# m0xpdLooping_ADSR_v2_0.net
KiCad netlist of a schematic drawn in EAGLE
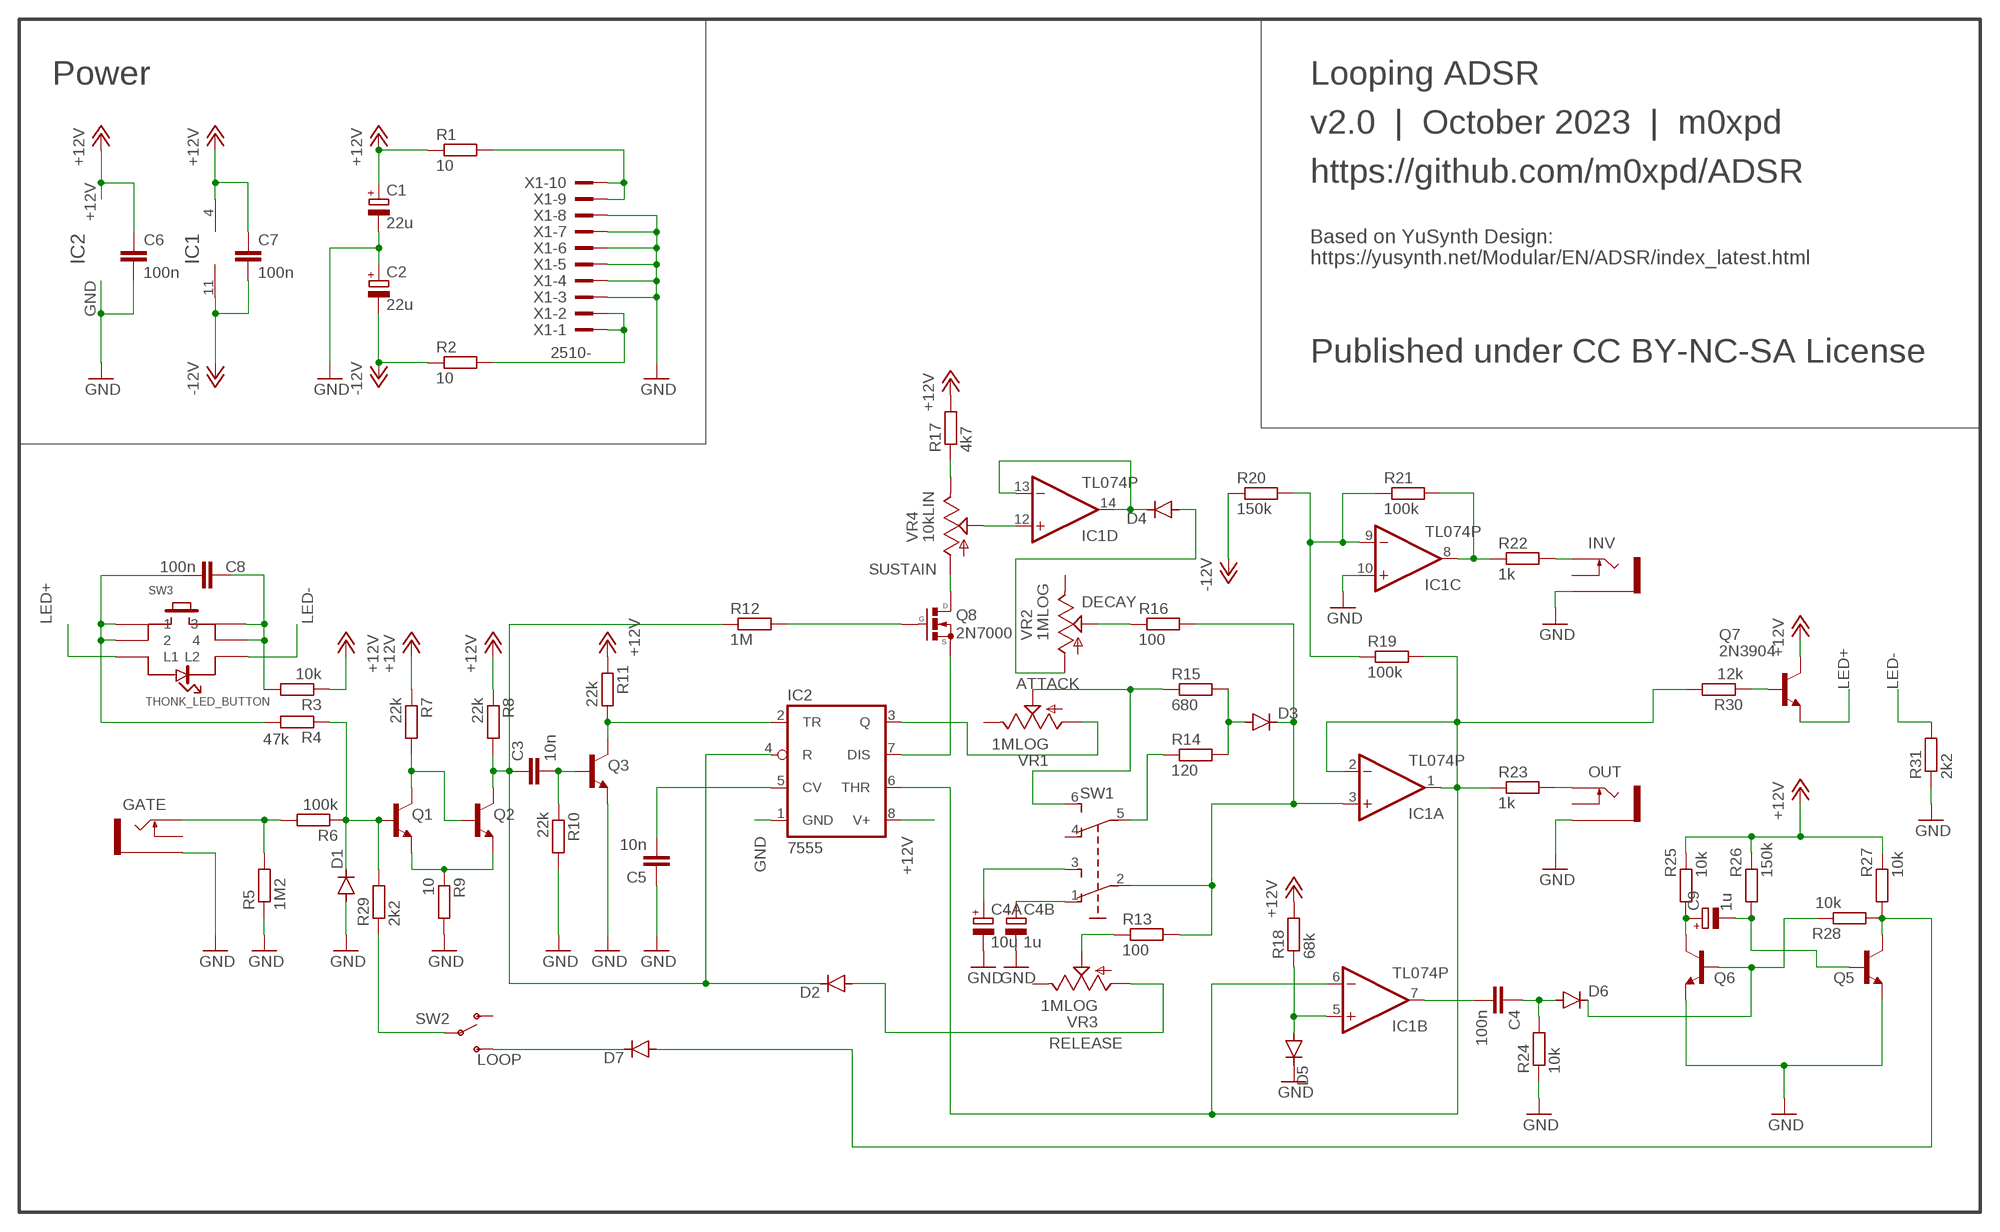
[diagram p0: schematic, sheet 1]

(export (version "E")
  (design (tool "Eeschema 10.0.6"))
  (components
    (comp (ref "C1")
      (value "22u")
      (footprint "eagle-import:E2,5-5")
      (libsource (lib "eagle-import") (part "CPOL-EUE2.5-5"))
    )
    (comp (ref "C2")
      (value "22u")
      (footprint "eagle-import:E2,5-5")
      (libsource (lib "eagle-import") (part "CPOL-EUE2.5-5"))
    )
    (comp (ref "C3")
      (value "10n")
      (footprint "eagle-import:C050-025X075")
      (libsource (lib "eagle-import") (part "C-EU050-025X075"))
    )
    (comp (ref "C4")
      (value "100n")
      (footprint "eagle-import:C050-025X075")
      (libsource (lib "eagle-import") (part "C-EU050-025X075"))
    )
    (comp (ref "C4A")
      (value "10u")
      (footprint "eagle-import:E2,5-5")
      (libsource (lib "eagle-import") (part "CPOL-EUE2.5-5"))
    )
    (comp (ref "C4B")
      (value "1u")
      (footprint "eagle-import:E2,5-5")
      (libsource (lib "eagle-import") (part "CPOL-EUE2.5-5"))
    )
    (comp (ref "C5")
      (value "10n")
      (footprint "eagle-import:C050-025X075")
      (libsource (lib "eagle-import") (part "C-EU050-025X075"))
    )
    (comp (ref "C6")
      (value "100n")
      (footprint "eagle-import:C050-025X075")
      (libsource (lib "eagle-import") (part "C-EU050-025X075"))
    )
    (comp (ref "C7")
      (value "100n")
      (footprint "eagle-import:C050-025X075")
      (libsource (lib "eagle-import") (part "C-EU050-025X075"))
    )
    (comp (ref "C8")
      (value "100n")
      (footprint "eagle-import:C025-030X050")
      (libsource (lib "eagle-import") (part "C-EU025-030X050"))
    )
    (comp (ref "C9")
      (value "1u")
      (footprint "eagle-import:E2,5-5")
      (libsource (lib "eagle-import") (part "CPOL-EUE2.5-5"))
    )
    (comp (ref "D1")
      (value "1N4148DO35-7")
      (footprint "eagle-import:DO35-7")
      (libsource (lib "eagle-import") (part "1N4148DO35-7"))
    )
    (comp (ref "D2")
      (value "1N4148DO35-7")
      (footprint "eagle-import:DO35-7")
      (libsource (lib "eagle-import") (part "1N4148DO35-7"))
    )
    (comp (ref "D3")
      (value "1N4148DO35-7")
      (footprint "eagle-import:DO35-7")
      (libsource (lib "eagle-import") (part "1N4148DO35-7"))
    )
    (comp (ref "D4")
      (value "1N4148DO35-7")
      (footprint "eagle-import:DO35-7")
      (libsource (lib "eagle-import") (part "1N4148DO35-7"))
    )
    (comp (ref "D5")
      (value "1N4148DO35-7")
      (footprint "eagle-import:DO35-7")
      (libsource (lib "eagle-import") (part "1N4148DO35-7"))
    )
    (comp (ref "D6")
      (value "1N4148DO35-7")
      (footprint "eagle-import:DO35-7")
      (libsource (lib "eagle-import") (part "1N4148DO35-7"))
    )
    (comp (ref "D7")
      (value "1N4148DO35-7")
      (footprint "eagle-import:DO35-7")
      (libsource (lib "eagle-import") (part "1N4148DO35-7"))
    )
    (comp (ref "GATE")
      (value "THONKICONNNEW")
      (footprint "eagle-import:WQP-PJ301M-12_JACK")
      (libsource (lib "eagle-import") (part "THONKICONNNEW"))
    )
    (comp (ref "IC1")
      (value "TL074P")
      (footprint "eagle-import:DIL14")
      (libsource (lib "eagle-import") (part "TL074P"))
    )
    (comp (ref "IC2")
      (value "7555")
      (footprint "eagle-import:DIL08")
      (libsource (lib "eagle-import") (part "7555"))
    )
    (comp (ref "INV")
      (value "THONKICONNNEW")
      (footprint "eagle-import:WQP-PJ301M-12_JACK")
      (libsource (lib "eagle-import") (part "THONKICONNNEW"))
    )
    (comp (ref "OUT")
      (value "THONKICONNNEW")
      (footprint "eagle-import:WQP-PJ301M-12_JACK")
      (libsource (lib "eagle-import") (part "THONKICONNNEW"))
    )
    (comp (ref "Q1")
      (value "2N3904")
      (footprint "eagle-import:TO92")
      (libsource (lib "eagle-import") (part "2N3904"))
    )
    (comp (ref "Q2")
      (value "2N3904")
      (footprint "eagle-import:TO92")
      (libsource (lib "eagle-import") (part "2N3904"))
    )
    (comp (ref "Q3")
      (value "2N3904")
      (footprint "eagle-import:TO92")
      (libsource (lib "eagle-import") (part "2N3904"))
    )
    (comp (ref "Q5")
      (value "2N3904")
      (footprint "eagle-import:TO92")
      (libsource (lib "eagle-import") (part "2N3904"))
    )
    (comp (ref "Q6")
      (value "2N3904")
      (footprint "eagle-import:TO92")
      (libsource (lib "eagle-import") (part "2N3904"))
    )
    (comp (ref "Q7")
      (value "2N3904")
      (footprint "eagle-import:TO92")
      (libsource (lib "eagle-import") (part "2N3904"))
    )
    (comp (ref "Q8")
      (value "2N7000")
      (footprint "eagle-import:TO92")
      (libsource (lib "eagle-import") (part "2N7000"))
    )
    (comp (ref "R1")
      (value "10")
      (footprint "eagle-import:0204_7")
      (libsource (lib "eagle-import") (part "R-EU_0204/7"))
    )
    (comp (ref "R2")
      (value "10")
      (footprint "eagle-import:0204_7")
      (libsource (lib "eagle-import") (part "R-EU_0204/7"))
    )
    (comp (ref "R3")
      (value "10k")
      (footprint "eagle-import:0204_7")
      (libsource (lib "eagle-import") (part "R-EU_0204/7"))
    )
    (comp (ref "R4")
      (value "47k")
      (footprint "eagle-import:0204_7")
      (libsource (lib "eagle-import") (part "R-EU_0204/7"))
    )
    (comp (ref "R5")
      (value "1M2")
      (footprint "eagle-import:0204_7")
      (libsource (lib "eagle-import") (part "R-EU_0204/7"))
    )
    (comp (ref "R6")
      (value "100k")
      (footprint "eagle-import:0204_7")
      (libsource (lib "eagle-import") (part "R-EU_0204/7"))
    )
    (comp (ref "R7")
      (value "22k")
      (footprint "eagle-import:0204_7")
      (libsource (lib "eagle-import") (part "R-EU_0204/7"))
    )
    (comp (ref "R8")
      (value "22k")
      (footprint "eagle-import:0204_7")
      (libsource (lib "eagle-import") (part "R-EU_0204/7"))
    )
    (comp (ref "R9")
      (value "10")
      (footprint "eagle-import:0204_7")
      (libsource (lib "eagle-import") (part "R-EU_0204/7"))
    )
    (comp (ref "R10")
      (value "22k")
      (footprint "eagle-import:0204_7")
      (libsource (lib "eagle-import") (part "R-EU_0204/7"))
    )
    (comp (ref "R11")
      (value "22k")
      (footprint "eagle-import:0204_7")
      (libsource (lib "eagle-import") (part "R-EU_0204/7"))
    )
    (comp (ref "R12")
      (value "1M")
      (footprint "eagle-import:0204_7")
      (libsource (lib "eagle-import") (part "R-EU_0204/7"))
    )
    (comp (ref "R13")
      (value "100")
      (footprint "eagle-import:0204_7")
      (libsource (lib "eagle-import") (part "R-EU_0204/7"))
    )
    (comp (ref "R14")
      (value "120")
      (footprint "eagle-import:0204_7")
      (libsource (lib "eagle-import") (part "R-EU_0204/7"))
    )
    (comp (ref "R15")
      (value "680")
      (footprint "eagle-import:0204_7")
      (libsource (lib "eagle-import") (part "R-EU_0204/7"))
    )
    (comp (ref "R16")
      (value "100")
      (footprint "eagle-import:0204_7")
      (libsource (lib "eagle-import") (part "R-EU_0204/7"))
    )
    (comp (ref "R17")
      (value "4k7")
      (footprint "eagle-import:0204_7")
      (libsource (lib "eagle-import") (part "R-EU_0204/7"))
    )
    (comp (ref "R18")
      (value "68k")
      (footprint "eagle-import:0204_7")
      (libsource (lib "eagle-import") (part "R-EU_0204/7"))
    )
    (comp (ref "R19")
      (value "100k")
      (footprint "eagle-import:0204_7")
      (libsource (lib "eagle-import") (part "R-EU_0204/7"))
    )
    (comp (ref "R20")
      (value "150k")
      (footprint "eagle-import:0204_7")
      (libsource (lib "eagle-import") (part "R-EU_0204/7"))
    )
    (comp (ref "R21")
      (value "100k")
      (footprint "eagle-import:0204_7")
      (libsource (lib "eagle-import") (part "R-EU_0204/7"))
    )
    (comp (ref "R22")
      (value "1k")
      (footprint "eagle-import:0204_7")
      (libsource (lib "eagle-import") (part "R-EU_0204/7"))
    )
    (comp (ref "R23")
      (value "1k")
      (footprint "eagle-import:0204_7")
      (libsource (lib "eagle-import") (part "R-EU_0204/7"))
    )
    (comp (ref "R24")
      (value "10k")
      (footprint "eagle-import:0204_7")
      (libsource (lib "eagle-import") (part "R-EU_0204/7"))
    )
    (comp (ref "R25")
      (value "10k")
      (footprint "eagle-import:0204_7")
      (libsource (lib "eagle-import") (part "R-EU_0204/7"))
    )
    (comp (ref "R26")
      (value "150k")
      (footprint "eagle-import:0204_7")
      (libsource (lib "eagle-import") (part "R-EU_0204/7"))
    )
    (comp (ref "R27")
      (value "10k")
      (footprint "eagle-import:0204_7")
      (libsource (lib "eagle-import") (part "R-EU_0204/7"))
    )
    (comp (ref "R28")
      (value "10k")
      (footprint "eagle-import:0204_7")
      (libsource (lib "eagle-import") (part "R-EU_0204/7"))
    )
    (comp (ref "R29")
      (value "2k2")
      (footprint "eagle-import:0204_7")
      (libsource (lib "eagle-import") (part "R-EU_0204/7"))
    )
    (comp (ref "R30")
      (value "12k")
      (footprint "eagle-import:0204_7")
      (libsource (lib "eagle-import") (part "R-EU_0204/7"))
    )
    (comp (ref "R31")
      (value "2k2")
      (footprint "eagle-import:0204_7")
      (libsource (lib "eagle-import") (part "R-EU_0204/7"))
    )
    (comp (ref "SW1")
      (value "TL46PO")
      (footprint "eagle-import:TL4XPO")
      (libsource (lib "eagle-import") (part "TL46PO"))
    )
    (comp (ref "SW2")
      (value "SUBMINI_SPDT")
      (footprint "eagle-import:SUBMINI_TOGGLE")
      (libsource (lib "eagle-import") (part "SUBMINI_SPDT"))
    )
    (comp (ref "SW3")
      (value "THONK_LED_BUTTON")
      (footprint "eagle-import:LOW_PROFILE_BUTTON")
      (libsource (lib "eagle-import") (part "THONK_LED_BUTTON"))
    )
    (comp (ref "VR1")
      (value "1MLOG")
      (footprint "eagle-import:9MM_SNAP-IN_POT")
      (libsource (lib "eagle-import") (part "9MM_SNAP-IN_POT_"))
    )
    (comp (ref "VR2")
      (value "1MLOG")
      (footprint "eagle-import:9MM_SNAP-IN_POT")
      (libsource (lib "eagle-import") (part "9MM_SNAP-IN_POT_"))
    )
    (comp (ref "VR3")
      (value "1MLOG")
      (footprint "eagle-import:9MM_SNAP-IN_POT")
      (libsource (lib "eagle-import") (part "9MM_SNAP-IN_POT_"))
    )
    (comp (ref "VR4")
      (value "10kLIN")
      (footprint "eagle-import:9MM_SNAP-IN_POT")
      (libsource (lib "eagle-import") (part "9MM_SNAP-IN_POT_"))
    )
    (comp (ref "X1")
      (value "2510-")
      (footprint "eagle-import:PAK100_2500-10")
      (fields (field (name "MF") "3M") (field (name "MPN") "2510-6002UB"))
      (libsource (lib "eagle-import") (part "2510-"))
    )
  )
  (nets
    (net (code "1") (name "+12V") (class "Default")
      (node (ref "C1") (pin "+") (pinfunction "+_+") (pintype "passive"))
      (node (ref "C6") (pin "1") (pinfunction "1_1") (pintype "passive"))
      (node (ref "C7") (pin "1") (pinfunction "1_1") (pintype "passive"))
      (node (ref "IC1") (pin "4") (pinfunction "V+_4") (pintype "power_in"))
      (node (ref "IC2") (pin "8") (pinfunction "V+_8") (pintype "power_in"))
      (node (ref "Q7") (pin "1") (pinfunction "C_1") (pintype "passive"))
      (node (ref "R1") (pin "1") (pinfunction "1_1") (pintype "passive"))
      (node (ref "R11") (pin "1") (pinfunction "1_1") (pintype "passive"))
      (node (ref "R17") (pin "2") (pinfunction "2_2") (pintype "passive"))
      (node (ref "R18") (pin "2") (pinfunction "2_2") (pintype "passive"))
      (node (ref "R25") (pin "2") (pinfunction "2_2") (pintype "passive"))
      (node (ref "R26") (pin "2") (pinfunction "2_2") (pintype "passive"))
      (node (ref "R27") (pin "2") (pinfunction "2_2") (pintype "passive"))
      (node (ref "R3") (pin "1") (pinfunction "1_1") (pintype "passive"))
      (node (ref "R7") (pin "1") (pinfunction "1_1") (pintype "passive"))
      (node (ref "R8") (pin "1") (pinfunction "1_1") (pintype "passive"))
    )
    (net (code "2") (name "-12V") (class "Default")
      (node (ref "C2") (pin "-") (pinfunction "-_-") (pintype "passive"))
      (node (ref "C7") (pin "2") (pinfunction "2_2") (pintype "passive"))
      (node (ref "IC1") (pin "11") (pinfunction "V-_11") (pintype "power_in"))
      (node (ref "R2") (pin "1") (pinfunction "1_1") (pintype "passive"))
      (node (ref "R20") (pin "1") (pinfunction "1_1") (pintype "passive"))
    )
    (net (code "3") (name "/LED+") (class "Default")
      (node (ref "Q7") (pin "3") (pinfunction "E_3") (pintype "passive"))
      (node (ref "SW3") (pin "L$1") (pinfunction "L1_L$1") (pintype "bidirectional"))
    )
    (net (code "4") (name "/LED-") (class "Default")
      (node (ref "R31") (pin "2") (pinfunction "2_2") (pintype "passive"))
      (node (ref "SW3") (pin "L$2") (pinfunction "L2_L$2") (pintype "bidirectional"))
    )
    (net (code "5") (name "GND") (class "Default")
      (node (ref "C1") (pin "-") (pinfunction "-_-") (pintype "passive"))
      (node (ref "C2") (pin "+") (pinfunction "+_+") (pintype "passive"))
      (node (ref "C4A") (pin "-") (pinfunction "-_-") (pintype "passive"))
      (node (ref "C4B") (pin "-") (pinfunction "-_-") (pintype "passive"))
      (node (ref "C5") (pin "1") (pinfunction "1_1") (pintype "passive"))
      (node (ref "C6") (pin "2") (pinfunction "2_2") (pintype "passive"))
      (node (ref "D1") (pin "A") (pinfunction "A_A") (pintype "passive"))
      (node (ref "D5") (pin "C") (pinfunction "C_C") (pintype "passive"))
      (node (ref "GATE") (pin "P$3_SLEEVE") (pinfunction "SLEEVE_P$3_SLEEVE") (pintype "passive"))
      (node (ref "IC1") (pin "10") (pinfunction "+IN_10") (pintype "input"))
      (node (ref "IC2") (pin "1") (pinfunction "GND_1") (pintype "power_in"))
      (node (ref "INV") (pin "P$3_SLEEVE") (pinfunction "SLEEVE_P$3_SLEEVE") (pintype "passive"))
      (node (ref "OUT") (pin "P$3_SLEEVE") (pinfunction "SLEEVE_P$3_SLEEVE") (pintype "passive"))
      (node (ref "Q3") (pin "3") (pinfunction "E_3") (pintype "passive"))
      (node (ref "Q5") (pin "3") (pinfunction "E_3") (pintype "passive"))
      (node (ref "Q6") (pin "3") (pinfunction "E_3") (pintype "passive"))
      (node (ref "R10") (pin "2") (pinfunction "2_2") (pintype "passive"))
      (node (ref "R24") (pin "1") (pinfunction "1_1") (pintype "passive"))
      (node (ref "R31") (pin "1") (pinfunction "1_1") (pintype "passive"))
      (node (ref "R5") (pin "1") (pinfunction "1_1") (pintype "passive"))
      (node (ref "R9") (pin "2") (pinfunction "2_2") (pintype "passive"))
      (node (ref "X1") (pin "3") (pinfunction "KL_3") (pintype "passive"))
      (node (ref "X1") (pin "4") (pinfunction "KL_4") (pintype "passive"))
      (node (ref "X1") (pin "5") (pinfunction "KL_5") (pintype "passive"))
      (node (ref "X1") (pin "6") (pinfunction "KL_6") (pintype "passive"))
      (node (ref "X1") (pin "7") (pinfunction "KL_7") (pintype "passive"))
      (node (ref "X1") (pin "8") (pinfunction "KL_8") (pintype "passive"))
    )
    (net (code "6") (name "Net-(C4-Pad1)") (class "Default")
      (node (ref "C4") (pin "1") (pinfunction "1_1") (pintype "passive"))
      (node (ref "D6") (pin "A") (pinfunction "A_A") (pintype "passive"))
      (node (ref "R24") (pin "2") (pinfunction "2_2") (pintype "passive"))
    )
    (net (code "7") (name "Net-(D3-PadA)") (class "Default")
      (node (ref "D3") (pin "A") (pinfunction "A_A") (pintype "passive"))
      (node (ref "R14") (pin "2") (pinfunction "2_2") (pintype "passive"))
      (node (ref "R15") (pin "2") (pinfunction "2_2") (pintype "passive"))
    )
    (net (code "8") (name "Net-(GATE-TIP)") (class "Default")
      (node (ref "GATE") (pin "P$1_TIP") (pinfunction "TIP_P$1_TIP") (pintype "passive"))
      (node (ref "R5") (pin "2") (pinfunction "2_2") (pintype "passive"))
      (node (ref "R6") (pin "2") (pinfunction "2_2") (pintype "passive"))
    )
    (net (code "9") (name "Net-(IC1A-+IN)") (class "Default")
      (node (ref "D3") (pin "C") (pinfunction "C_C") (pintype "passive"))
      (node (ref "IC1") (pin "3") (pinfunction "+IN_3") (pintype "input"))
      (node (ref "R13") (pin "2") (pinfunction "2_2") (pintype "passive"))
      (node (ref "R16") (pin "2") (pinfunction "2_2") (pintype "passive"))
      (node (ref "SW1") (pin "2") (pinfunction "P_2") (pintype "passive"))
    )
    (net (code "10") (name "Net-(IC1A--IN)") (class "Default")
      (node (ref "IC1") (pin "1") (pinfunction "OUT_1") (pintype "output"))
      (node (ref "IC1") (pin "2") (pinfunction "-IN_2") (pintype "input"))
      (node (ref "IC1") (pin "6") (pinfunction "-IN_6") (pintype "input"))
      (node (ref "IC2") (pin "6") (pinfunction "THR_6") (pintype "input"))
      (node (ref "R19") (pin "2") (pinfunction "2_2") (pintype "passive"))
      (node (ref "R23") (pin "1") (pinfunction "1_1") (pintype "passive"))
      (node (ref "R30") (pin "2") (pinfunction "2_2") (pintype "passive"))
    )
    (net (code "11") (name "Net-(IC1B-+IN)") (class "Default")
      (node (ref "D5") (pin "A") (pinfunction "A_A") (pintype "passive"))
      (node (ref "IC1") (pin "5") (pinfunction "+IN_5") (pintype "input"))
      (node (ref "R18") (pin "1") (pinfunction "1_1") (pintype "passive"))
    )
    (net (code "12") (name "Net-(IC1B-OUT)") (class "Default")
      (node (ref "C4") (pin "2") (pinfunction "2_2") (pintype "passive"))
      (node (ref "IC1") (pin "7") (pinfunction "OUT_7") (pintype "output"))
    )
    (net (code "13") (name "Net-(IC1C--IN)") (class "Default")
      (node (ref "IC1") (pin "9") (pinfunction "-IN_9") (pintype "input"))
      (node (ref "R19") (pin "1") (pinfunction "1_1") (pintype "passive"))
      (node (ref "R20") (pin "2") (pinfunction "2_2") (pintype "passive"))
      (node (ref "R21") (pin "1") (pinfunction "1_1") (pintype "passive"))
    )
    (net (code "14") (name "Net-(IC1C-OUT)") (class "Default")
      (node (ref "IC1") (pin "8") (pinfunction "OUT_8") (pintype "output"))
      (node (ref "R21") (pin "2") (pinfunction "2_2") (pintype "passive"))
      (node (ref "R22") (pin "1") (pinfunction "1_1") (pintype "passive"))
    )
    (net (code "15") (name "Net-(IC1D-+IN)") (class "Default")
      (node (ref "IC1") (pin "12") (pinfunction "+IN_12") (pintype "input"))
      (node (ref "VR4") (pin "2") (pinfunction "S_2") (pintype "passive"))
    )
    (net (code "16") (name "Net-(IC1D--IN)") (class "Default")
      (node (ref "D4") (pin "C") (pinfunction "C_C") (pintype "passive"))
      (node (ref "IC1") (pin "13") (pinfunction "-IN_13") (pintype "input"))
      (node (ref "IC1") (pin "14") (pinfunction "OUT_14") (pintype "output"))
    )
    (net (code "17") (name "Net-(IC2-CV)") (class "Default")
      (node (ref "C5") (pin "2") (pinfunction "2_2") (pintype "passive"))
      (node (ref "IC2") (pin "5") (pinfunction "CV_5") (pintype "input"))
    )
    (net (code "18") (name "Net-(IC2-DIS)") (class "Default")
      (node (ref "IC2") (pin "7") (pinfunction "DIS_7") (pintype "input"))
      (node (ref "Q8") (pin "1") (pinfunction "S_1") (pintype "passive"))
    )
    (net (code "19") (name "Net-(IC2-Q)") (class "Default")
      (node (ref "IC2") (pin "3") (pinfunction "Q_3") (pintype "output"))
      (node (ref "VR1") (pin "1") (pinfunction "A_1") (pintype "passive"))
    )
    (net (code "20") (name "Net-(IC2-R)") (class "Default")
      (node (ref "C3") (pin "1") (pinfunction "1_1") (pintype "passive"))
      (node (ref "D2") (pin "C") (pinfunction "C_C") (pintype "passive"))
      (node (ref "IC2") (pin "4") (pinfunction "R_4") (pintype "input"))
      (node (ref "Q2") (pin "1") (pinfunction "C_1") (pintype "passive"))
      (node (ref "R12") (pin "1") (pinfunction "1_1") (pintype "passive"))
      (node (ref "R8") (pin "2") (pinfunction "2_2") (pintype "passive"))
    )
    (net (code "21") (name "Net-(IC2-TR)") (class "Default")
      (node (ref "IC2") (pin "2") (pinfunction "TR_2") (pintype "input"))
      (node (ref "Q3") (pin "1") (pinfunction "C_1") (pintype "passive"))
      (node (ref "R11") (pin "2") (pinfunction "2_2") (pintype "passive"))
    )
    (net (code "22") (name "Net-(INV-TIP)") (class "Default")
      (node (ref "INV") (pin "P$1_TIP") (pinfunction "TIP_P$1_TIP") (pintype "passive"))
      (node (ref "R22") (pin "2") (pinfunction "2_2") (pintype "passive"))
    )
    (net (code "23") (name "Net-(OUT-TIP)") (class "Default")
      (node (ref "OUT") (pin "P$1_TIP") (pinfunction "TIP_P$1_TIP") (pintype "passive"))
      (node (ref "R23") (pin "2") (pinfunction "2_2") (pintype "passive"))
    )
    (net (code "24") (name "Net-(Q1-B)") (class "Default")
      (node (ref "D1") (pin "C") (pinfunction "C_C") (pintype "passive"))
      (node (ref "Q1") (pin "2") (pinfunction "B_2") (pintype "passive"))
      (node (ref "R29") (pin "2") (pinfunction "2_2") (pintype "passive"))
      (node (ref "R4") (pin "1") (pinfunction "1_1") (pintype "passive"))
      (node (ref "R6") (pin "1") (pinfunction "1_1") (pintype "passive"))
    )
    (net (code "25") (name "Net-(Q1-C)") (class "Default")
      (node (ref "Q1") (pin "1") (pinfunction "C_1") (pintype "passive"))
      (node (ref "Q2") (pin "2") (pinfunction "B_2") (pintype "passive"))
      (node (ref "R7") (pin "2") (pinfunction "2_2") (pintype "passive"))
    )
    (net (code "26") (name "Net-(Q1-E)") (class "Default")
      (node (ref "Q1") (pin "3") (pinfunction "E_3") (pintype "passive"))
      (node (ref "Q2") (pin "3") (pinfunction "E_3") (pintype "passive"))
      (node (ref "R9") (pin "1") (pinfunction "1_1") (pintype "passive"))
    )
    (net (code "27") (name "Net-(Q3-B)") (class "Default")
      (node (ref "C3") (pin "2") (pinfunction "2_2") (pintype "passive"))
      (node (ref "Q3") (pin "2") (pinfunction "B_2") (pintype "passive"))
      (node (ref "R10") (pin "1") (pinfunction "1_1") (pintype "passive"))
    )
    (net (code "28") (name "Net-(Q5-B)") (class "Default")
      (node (ref "C9") (pin "-") (pinfunction "-_-") (pintype "passive"))
      (node (ref "Q5") (pin "2") (pinfunction "B_2") (pintype "passive"))
      (node (ref "R26") (pin "1") (pinfunction "1_1") (pintype "passive"))
    )
    (net (code "29") (name "Net-(Q5-C)") (class "Default")
      (node (ref "D7") (pin "A") (pinfunction "A_A") (pintype "passive"))
      (node (ref "Q5") (pin "1") (pinfunction "C_1") (pintype "passive"))
      (node (ref "R27") (pin "1") (pinfunction "1_1") (pintype "passive"))
      (node (ref "R28") (pin "1") (pinfunction "1_1") (pintype "passive"))
    )
    (net (code "30") (name "Net-(Q6-B)") (class "Default")
      (node (ref "D6") (pin "C") (pinfunction "C_C") (pintype "passive"))
      (node (ref "Q6") (pin "2") (pinfunction "B_2") (pintype "passive"))
      (node (ref "R28") (pin "2") (pinfunction "2_2") (pintype "passive"))
    )
    (net (code "31") (name "Net-(Q6-C)") (class "Default")
      (node (ref "C9") (pin "+") (pinfunction "+_+") (pintype "passive"))
      (node (ref "Q6") (pin "1") (pinfunction "C_1") (pintype "passive"))
      (node (ref "R25") (pin "1") (pinfunction "1_1") (pintype "passive"))
    )
    (net (code "32") (name "Net-(Q7-B)") (class "Default")
      (node (ref "Q7") (pin "2") (pinfunction "B_2") (pintype "passive"))
      (node (ref "R30") (pin "1") (pinfunction "1_1") (pintype "passive"))
    )
    (net (code "33") (name "Net-(Q8-D)") (class "Default")
      (node (ref "Q8") (pin "3") (pinfunction "D_3") (pintype "passive"))
      (node (ref "VR4") (pin "1") (pinfunction "A_1") (pintype "passive"))
    )
    (net (code "34") (name "Net-(Q8-G)") (class "Default")
      (node (ref "Q8") (pin "2") (pinfunction "G_2") (pintype "passive"))
      (node (ref "R12") (pin "2") (pinfunction "2_2") (pintype "passive"))
    )
    (net (code "35") (name "Net-(SW1-O)") (class "Default")
      (node (ref "C4B") (pin "+") (pinfunction "+_+") (pintype "passive"))
      (node (ref "SW1") (pin "1") (pinfunction "O_1") (pintype "passive"))
    )
    (net (code "36") (name "Net-(SW1-P1)") (class "Default")
      (node (ref "R14") (pin "1") (pinfunction "1_1") (pintype "passive"))
      (node (ref "SW1") (pin "5") (pinfunction "P1_5") (pintype "passive"))
    )
    (net (code "37") (name "Net-(SW1-S)") (class "Default")
      (node (ref "C4A") (pin "+") (pinfunction "+_+") (pintype "passive"))
      (node (ref "SW1") (pin "3") (pinfunction "S_3") (pintype "passive"))
    )
    (net (code "38") (name "Net-(SW1-S1)") (class "Default")
      (node (ref "R15") (pin "1") (pinfunction "1_1") (pintype "passive"))
      (node (ref "SW1") (pin "6") (pinfunction "S1_6") (pintype "passive"))
      (node (ref "VR1") (pin "2") (pinfunction "S_2") (pintype "passive"))
    )
    (net (code "39") (name "Net-(SW2-COMMON)") (class "Default")
      (node (ref "R29") (pin "1") (pinfunction "1_1") (pintype "passive"))
      (node (ref "SW2") (pin "COM") (pinfunction "COMMON_COM") (pintype "passive"))
    )
    (net (code "40") (name "Net-(SW2-S)") (class "Default")
      (node (ref "D7") (pin "C") (pinfunction "C_C") (pintype "passive"))
      (node (ref "SW2") (pin "3") (pinfunction "S_3") (pintype "passive"))
    )
    (net (code "41") (name "Net-(SW3-1)") (class "Default")
      (node (ref "C8") (pin "2") (pinfunction "2_2") (pintype "passive"))
      (node (ref "R4") (pin "2") (pinfunction "2_2") (pintype "passive"))
      (node (ref "SW3") (pin "P$1") (pinfunction "1_P$1") (pintype "bidirectional"))
      (node (ref "SW3") (pin "P$2") (pinfunction "2_P$2") (pintype "bidirectional"))
    )
    (net (code "42") (name "Net-(SW3-3)") (class "Default")
      (node (ref "C8") (pin "1") (pinfunction "1_1") (pintype "passive"))
      (node (ref "R3") (pin "2") (pinfunction "2_2") (pintype "passive"))
      (node (ref "SW3") (pin "P$3") (pinfunction "3_P$3") (pintype "bidirectional"))
      (node (ref "SW3") (pin "P$4") (pinfunction "4_P$4") (pintype "bidirectional"))
    )
    (net (code "43") (name "Net-(VR2-A)") (class "Default")
      (node (ref "D4") (pin "A") (pinfunction "A_A") (pintype "passive"))
      (node (ref "VR2") (pin "1") (pinfunction "A_1") (pintype "passive"))
    )
    (net (code "44") (name "Net-(VR2-S)") (class "Default")
      (node (ref "R16") (pin "1") (pinfunction "1_1") (pintype "passive"))
      (node (ref "VR2") (pin "2") (pinfunction "S_2") (pintype "passive"))
    )
    (net (code "45") (name "Net-(VR3-A)") (class "Default")
      (node (ref "D2") (pin "A") (pinfunction "A_A") (pintype "passive"))
      (node (ref "VR3") (pin "1") (pinfunction "A_1") (pintype "passive"))
    )
    (net (code "46") (name "Net-(VR3-S)") (class "Default")
      (node (ref "R13") (pin "1") (pinfunction "1_1") (pintype "passive"))
      (node (ref "VR3") (pin "2") (pinfunction "S_2") (pintype "passive"))
    )
    (net (code "47") (name "Net-(VR4-E)") (class "Default")
      (node (ref "R17") (pin "1") (pinfunction "1_1") (pintype "passive"))
      (node (ref "VR4") (pin "3") (pinfunction "E_3") (pintype "passive"))
    )
    (net (code "48") (name "Net-(X1A-KL)") (class "Default")
      (node (ref "R2") (pin "2") (pinfunction "2_2") (pintype "passive"))
      (node (ref "X1") (pin "1") (pinfunction "KL_1") (pintype "passive"))
      (node (ref "X1") (pin "2") (pinfunction "KL_2") (pintype "passive"))
    )
    (net (code "49") (name "Net-(X1B-KL)") (class "Default")
      (node (ref "R1") (pin "2") (pinfunction "2_2") (pintype "passive"))
      (node (ref "X1") (pin "10") (pinfunction "KL_10") (pintype "passive"))
      (node (ref "X1") (pin "9") (pinfunction "KL_9") (pintype "passive"))
    )
    (net (code "50") (name "unconnected-(GATE-SWITCH-PadP$2_SWITCH)") (class "Default")
      (node (ref "GATE") (pin "P$2_SWITCH") (pinfunction "SWITCH_P$2_SWITCH") (pintype "passive"))
    )
    (net (code "51") (name "unconnected-(INV-SWITCH-PadP$2_SWITCH)") (class "Default")
      (node (ref "INV") (pin "P$2_SWITCH") (pinfunction "SWITCH_P$2_SWITCH") (pintype "passive"))
    )
    (net (code "52") (name "unconnected-(OUT-SWITCH-PadP$2_SWITCH)") (class "Default")
      (node (ref "OUT") (pin "P$2_SWITCH") (pinfunction "SWITCH_P$2_SWITCH") (pintype "passive"))
    )
    (net (code "53") (name "unconnected-(SW1-O1-Pad4)") (class "Default")
      (node (ref "SW1") (pin "4") (pinfunction "O1_4") (pintype "passive"))
    )
    (net (code "54") (name "unconnected-(SW2-O-Pad1)") (class "Default")
      (node (ref "SW2") (pin "1") (pinfunction "O_1") (pintype "passive"))
    )
    (net (code "55") (name "unconnected-(VR1-E-Pad3)") (class "Default")
      (node (ref "VR1") (pin "3") (pinfunction "E_3") (pintype "passive"))
    )
    (net (code "56") (name "unconnected-(VR2-E-Pad3)") (class "Default")
      (node (ref "VR2") (pin "3") (pinfunction "E_3") (pintype "passive"))
    )
    (net (code "57") (name "unconnected-(VR3-E-Pad3)") (class "Default")
      (node (ref "VR3") (pin "3") (pinfunction "E_3") (pintype "passive"))
    )
  )
)
